# MR_UartConnector.net
KiCad netlist of a schematic drawn in Altium Designer
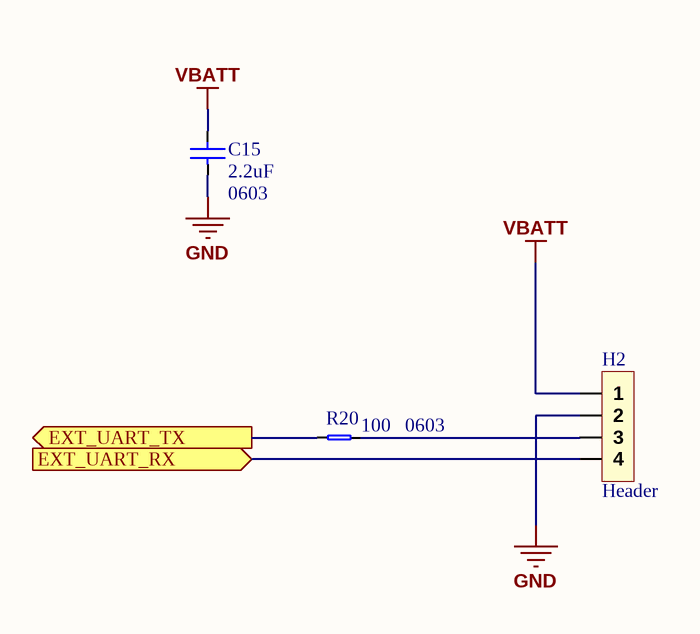
[diagram p0: MR_UartConnector.SchDoc]

(export (version "E")
  (design (tool "Eeschema 10.0.6"))
  (components
    (comp (ref "C15")
      (value "2.2uF")
      (footprint "0603_CAP_LD")
      (description "Ceramic Capacitor")
      (fields (field (name "PACKAGE") "0603") (field (name "Comment") "CerCap"))
      (libsource (lib "MiniRobot") (part "CerCap"))
    )
    (comp (ref "H2")
      (value "Header")
      (footprint "HE14 1x4 Straight")
      (description "Header 4x1 PIns")
      (libsource (lib "MiniRobot") (part "Header_4x1"))
    )
    (comp (ref "R20")
      (value "100")
      (footprint "0603_RES_LD")
      (description "Resistor")
      (fields (field (name "PACKAGE") "0603"))
      (libsource (lib "MiniRobot") (part "Resistor"))
    )
  )
  (nets
    (net (code "1") (name "/EXT_UART_RX") (class "Default")
      (node (ref "H2") (pin "4") (pinfunction "4_4") (pintype "passive"))
    )
    (net (code "2") (name "/EXT_UART_TX") (class "Default")
      (node (ref "R20") (pin "1") (pinfunction "1_1") (pintype "passive"))
    )
    (net (code "3") (name "GND") (class "Default")
      (node (ref "C15") (pin "1") (pinfunction "1_1") (pintype "passive"))
      (node (ref "H2") (pin "2") (pinfunction "2_2") (pintype "passive"))
    )
    (net (code "4") (name "Net-(H2-Pad3)") (class "Default")
      (node (ref "H2") (pin "3") (pinfunction "3_3") (pintype "passive"))
      (node (ref "R20") (pin "2") (pinfunction "2_2") (pintype "passive"))
    )
    (net (code "5") (name "VBATT") (class "Default")
      (node (ref "C15") (pin "2") (pinfunction "2_2") (pintype "passive"))
      (node (ref "H2") (pin "1") (pinfunction "1_1") (pintype "passive"))
    )
  )
)
